# Supplemental_Power_Switch_System.net
KiCad netlist of a schematic drawn in EAGLE
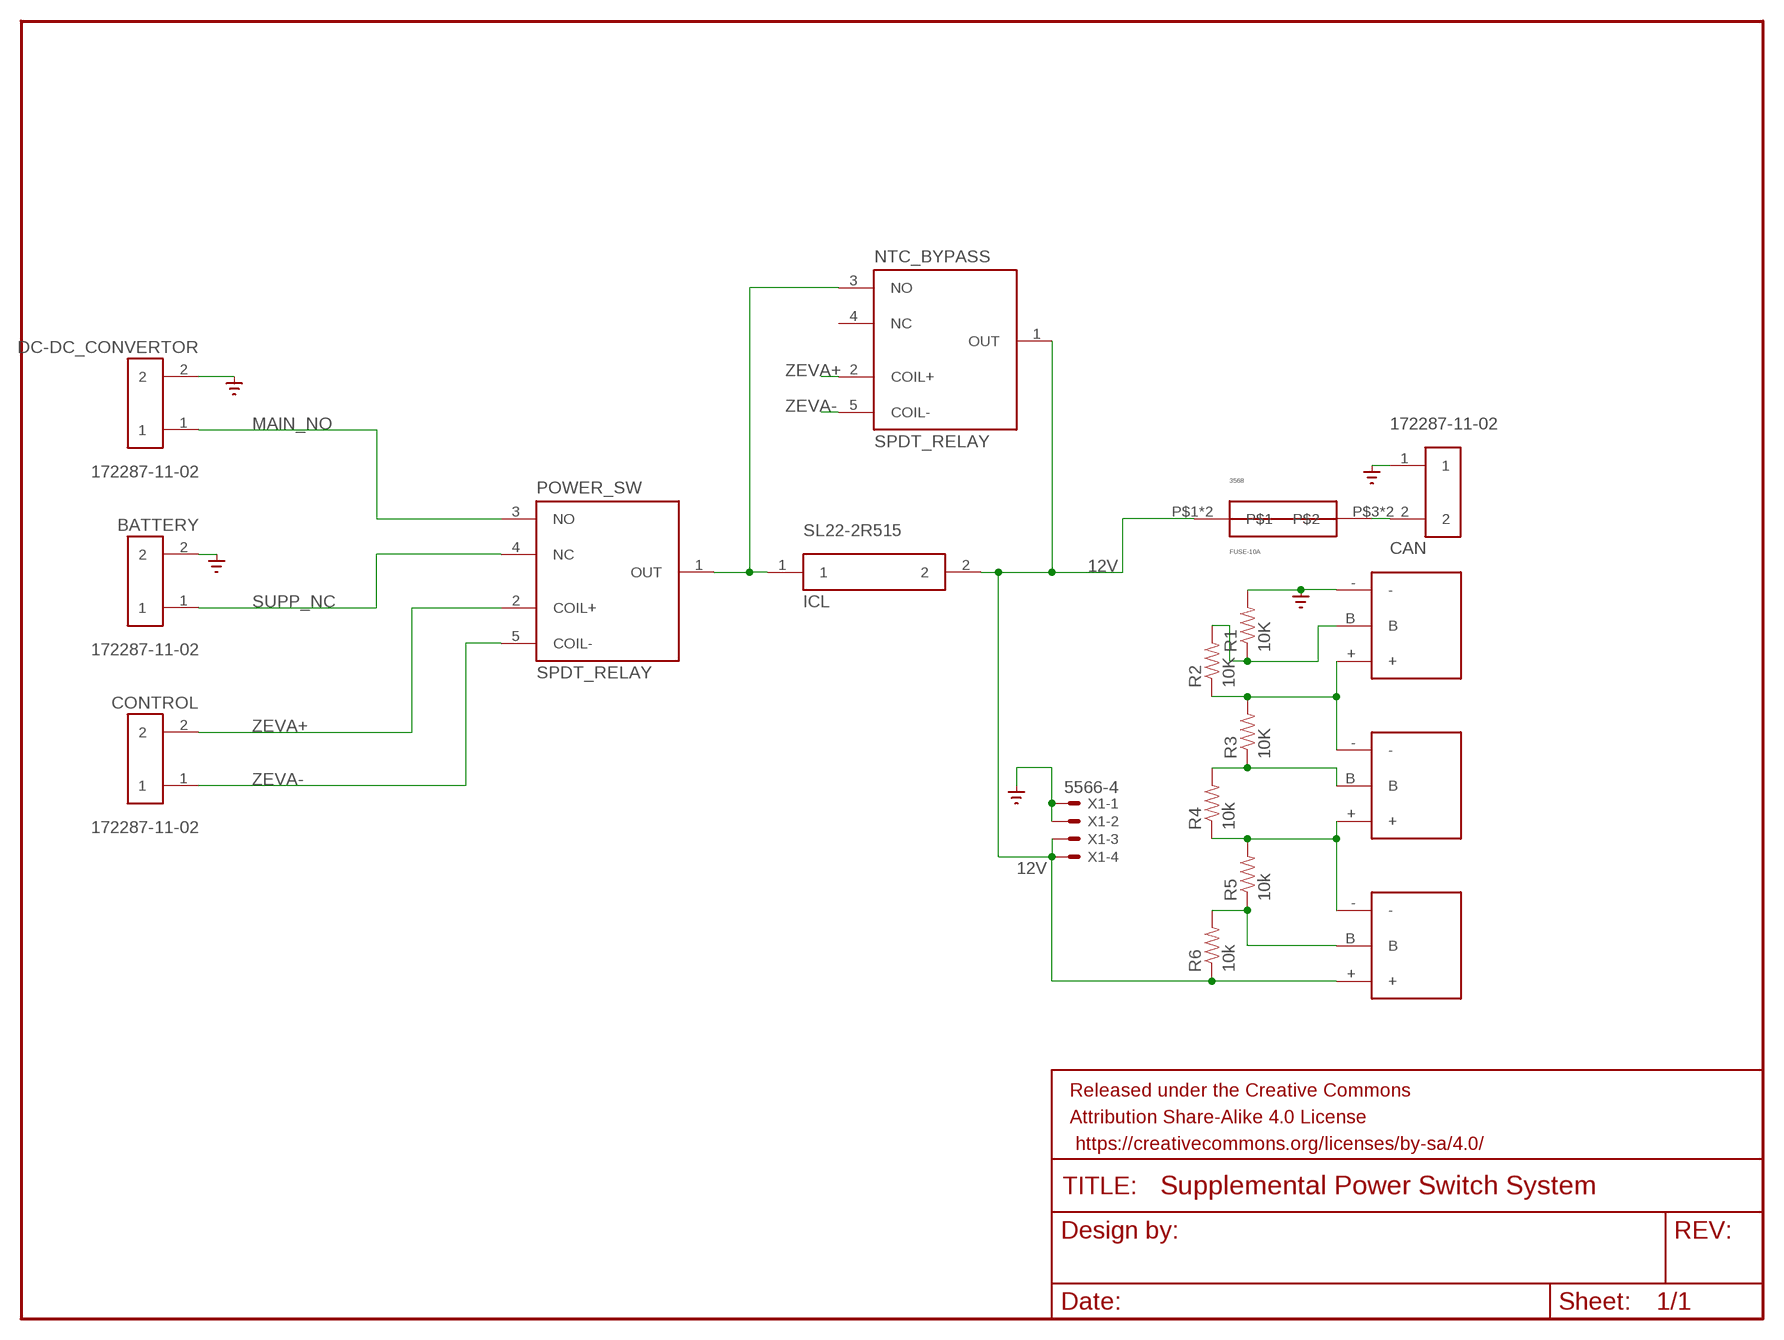
[diagram p0: schematic, sheet 1]

(export (version "E")
  (design (tool "Eeschema 10.0.6"))
  (components
    (comp (ref "BATTERY")
      (value "172287-11-02")
      (footprint "eagle-import:172287-ULTRA-FIT")
      (libsource (lib "eagle-import") (part "172287-11-02"))
    )
    (comp (ref "C1")
      (value "SUPER-CAPACITOR")
      (footprint "eagle-import:DMF")
      (libsource (lib "eagle-import") (part "SUPER-CAPACITOR"))
    )
    (comp (ref "C2")
      (value "SUPER-CAPACITOR")
      (footprint "eagle-import:DMF")
      (libsource (lib "eagle-import") (part "SUPER-CAPACITOR"))
    )
    (comp (ref "C3")
      (value "SUPER-CAPACITOR")
      (footprint "eagle-import:DMF")
      (libsource (lib "eagle-import") (part "SUPER-CAPACITOR"))
    )
    (comp (ref "CAN")
      (value "172287-11-02")
      (footprint "eagle-import:172287-ULTRA-FIT")
      (libsource (lib "eagle-import") (part "172287-11-02"))
    )
    (comp (ref "CONTROL")
      (value "172287-11-02")
      (footprint "eagle-import:172287-ULTRA-FIT")
      (libsource (lib "eagle-import") (part "172287-11-02"))
    )
    (comp (ref "DC-DC_CONVERTOR")
      (value "172287-11-02")
      (footprint "eagle-import:172287-ULTRA-FIT")
      (libsource (lib "eagle-import") (part "172287-11-02"))
    )
    (comp (ref "FRAME1")
      (value "FRAME-LETTERNO_PACKAGE")
      (footprint "eagle-import:DUMMY")
      (fields (field (name "DESIGNER") "Nobody"))
      (libsource (lib "eagle-import") (part "FRAME-LETTERNO_PACKAGE"))
    )
    (comp (ref "FUSE-10A")
      (value "3568")
      (footprint "eagle-import:3568-MINI-297")
      (libsource (lib "eagle-import") (part "3568"))
    )
    (comp (ref "ICL")
      (value "SL22-2R515")
      (footprint "eagle-import:SL22-2R515")
      (libsource (lib "eagle-import") (part "SL22-2R515"))
    )
    (comp (ref "NTC_BYPASS")
      (value "SPDT_RELAY")
      (footprint "eagle-import:G8QN-1C4")
      (libsource (lib "eagle-import") (part "SPDT_RELAY"))
    )
    (comp (ref "POWER_SW")
      (value "SPDT_RELAY")
      (footprint "eagle-import:G8QN-1C4")
      (libsource (lib "eagle-import") (part "SPDT_RELAY"))
    )
    (comp (ref "R1")
      (value "10K")
      (footprint "eagle-import:1_6W-RES")
      (libsource (lib "eagle-import") (part "RESISTORPTH-1/6W"))
    )
    (comp (ref "R2")
      (value "10K")
      (footprint "eagle-import:1_6W-RES")
      (libsource (lib "eagle-import") (part "RESISTORPTH-1/6W"))
    )
    (comp (ref "R3")
      (value "10K")
      (footprint "eagle-import:1_6W-RES")
      (libsource (lib "eagle-import") (part "RESISTORPTH-1/6W"))
    )
    (comp (ref "R4")
      (value "10k")
      (footprint "eagle-import:1_6W-RES")
      (libsource (lib "eagle-import") (part "RESISTORPTH-1/6W"))
    )
    (comp (ref "R5")
      (value "10k")
      (footprint "eagle-import:1_6W-RES")
      (libsource (lib "eagle-import") (part "RESISTORPTH-1/6W"))
    )
    (comp (ref "R6")
      (value "10k")
      (footprint "eagle-import:1_6W-RES")
      (libsource (lib "eagle-import") (part "RESISTORPTH-1/6W"))
    )
    (comp (ref "X1")
      (value "5566-4")
      (footprint "eagle-import:5566-4")
      (libsource (lib "eagle-import") (part "5566-4"))
    )
  )
  (nets
    (net (code "1") (name "/12V") (class "Default")
      (node (ref "C3") (pin "+") (pinfunction "+_+") (pintype "bidirectional"))
      (node (ref "FUSE-10A") (pin "P$1") (pinfunction "P$1_P$1") (pintype "bidirectional"))
      (node (ref "FUSE-10A") (pin "P$2") (pinfunction "P$1_P$2") (pintype "bidirectional"))
      (node (ref "ICL") (pin "2") (pinfunction "2_2") (pintype "bidirectional"))
      (node (ref "NTC_BYPASS") (pin "1") (pinfunction "OUT_1") (pintype "output"))
      (node (ref "R6") (pin "1") (pinfunction "1_1") (pintype "passive"))
      (node (ref "X1") (pin "3") (pinfunction "S_3") (pintype "passive"))
      (node (ref "X1") (pin "4") (pinfunction "S_4") (pintype "passive"))
    )
    (net (code "2") (name "/MAIN_NO") (class "Default")
      (node (ref "DC-DC_CONVERTOR") (pin "1") (pinfunction "1_1") (pintype "bidirectional"))
      (node (ref "POWER_SW") (pin "3") (pinfunction "NO_3") (pintype "input"))
    )
    (net (code "3") (name "/SUPP_NC") (class "Default")
      (node (ref "BATTERY") (pin "1") (pinfunction "1_1") (pintype "bidirectional"))
      (node (ref "POWER_SW") (pin "4") (pinfunction "NC_4") (pintype "input"))
    )
    (net (code "4") (name "/ZEVA+") (class "Default")
      (node (ref "CONTROL") (pin "2") (pinfunction "2_2") (pintype "bidirectional"))
      (node (ref "NTC_BYPASS") (pin "2") (pinfunction "COIL+_2") (pintype "input"))
      (node (ref "POWER_SW") (pin "2") (pinfunction "COIL+_2") (pintype "input"))
    )
    (net (code "5") (name "/ZEVA-") (class "Default")
      (node (ref "CONTROL") (pin "1") (pinfunction "1_1") (pintype "bidirectional"))
      (node (ref "NTC_BYPASS") (pin "5") (pinfunction "COIL-_5") (pintype "input"))
      (node (ref "POWER_SW") (pin "5") (pinfunction "COIL-_5") (pintype "input"))
    )
    (net (code "6") (name "GND_") (class "Default")
      (node (ref "BATTERY") (pin "2") (pinfunction "2_2") (pintype "bidirectional"))
      (node (ref "C1") (pin "-") (pinfunction "-_-") (pintype "bidirectional"))
      (node (ref "CAN") (pin "1") (pinfunction "1_1") (pintype "bidirectional"))
      (node (ref "DC-DC_CONVERTOR") (pin "2") (pinfunction "2_2") (pintype "bidirectional"))
      (node (ref "R1") (pin "2") (pinfunction "2_2") (pintype "passive"))
      (node (ref "X1") (pin "1") (pinfunction "S_1") (pintype "passive"))
      (node (ref "X1") (pin "2") (pinfunction "S_2") (pintype "passive"))
    )
    (net (code "7") (name "Net-(C1-Pad+)") (class "Default")
      (node (ref "C1") (pin "+") (pinfunction "+_+") (pintype "bidirectional"))
      (node (ref "C2") (pin "-") (pinfunction "-_-") (pintype "bidirectional"))
      (node (ref "R2") (pin "1") (pinfunction "1_1") (pintype "passive"))
      (node (ref "R3") (pin "2") (pinfunction "2_2") (pintype "passive"))
    )
    (net (code "8") (name "Net-(C1-PadB)") (class "Default")
      (node (ref "C1") (pin "B") (pinfunction "B_B") (pintype "bidirectional"))
      (node (ref "R1") (pin "1") (pinfunction "1_1") (pintype "passive"))
      (node (ref "R2") (pin "2") (pinfunction "2_2") (pintype "passive"))
    )
    (net (code "9") (name "Net-(C2-Pad+)") (class "Default")
      (node (ref "C2") (pin "+") (pinfunction "+_+") (pintype "bidirectional"))
      (node (ref "C3") (pin "-") (pinfunction "-_-") (pintype "bidirectional"))
      (node (ref "R4") (pin "1") (pinfunction "1_1") (pintype "passive"))
      (node (ref "R5") (pin "2") (pinfunction "2_2") (pintype "passive"))
    )
    (net (code "10") (name "Net-(C2-PadB)") (class "Default")
      (node (ref "C2") (pin "B") (pinfunction "B_B") (pintype "bidirectional"))
      (node (ref "R3") (pin "1") (pinfunction "1_1") (pintype "passive"))
      (node (ref "R4") (pin "2") (pinfunction "2_2") (pintype "passive"))
    )
    (net (code "11") (name "Net-(C3-PadB)") (class "Default")
      (node (ref "C3") (pin "B") (pinfunction "B_B") (pintype "bidirectional"))
      (node (ref "R5") (pin "1") (pinfunction "1_1") (pintype "passive"))
      (node (ref "R6") (pin "2") (pinfunction "2_2") (pintype "passive"))
    )
    (net (code "12") (name "Net-(CAN-Pad2)") (class "Default")
      (node (ref "CAN") (pin "2") (pinfunction "2_2") (pintype "bidirectional"))
      (node (ref "FUSE-10A") (pin "P$3") (pinfunction "P$2_P$3") (pintype "bidirectional"))
      (node (ref "FUSE-10A") (pin "P$4") (pinfunction "P$2_P$4") (pintype "bidirectional"))
    )
    (net (code "13") (name "Net-(NTC_BYPASS-NO)") (class "Default")
      (node (ref "ICL") (pin "1") (pinfunction "1_1") (pintype "bidirectional"))
      (node (ref "NTC_BYPASS") (pin "3") (pinfunction "NO_3") (pintype "input"))
      (node (ref "POWER_SW") (pin "1") (pinfunction "OUT_1") (pintype "output"))
    )
    (net (code "14") (name "unconnected-(NTC_BYPASS-NC-Pad4)") (class "Default")
      (node (ref "NTC_BYPASS") (pin "4") (pinfunction "NC_4") (pintype "input"))
    )
  )
)
